# 4_USB-PD_Controller.net
KiCad netlist of a schematic drawn in Altium Designer
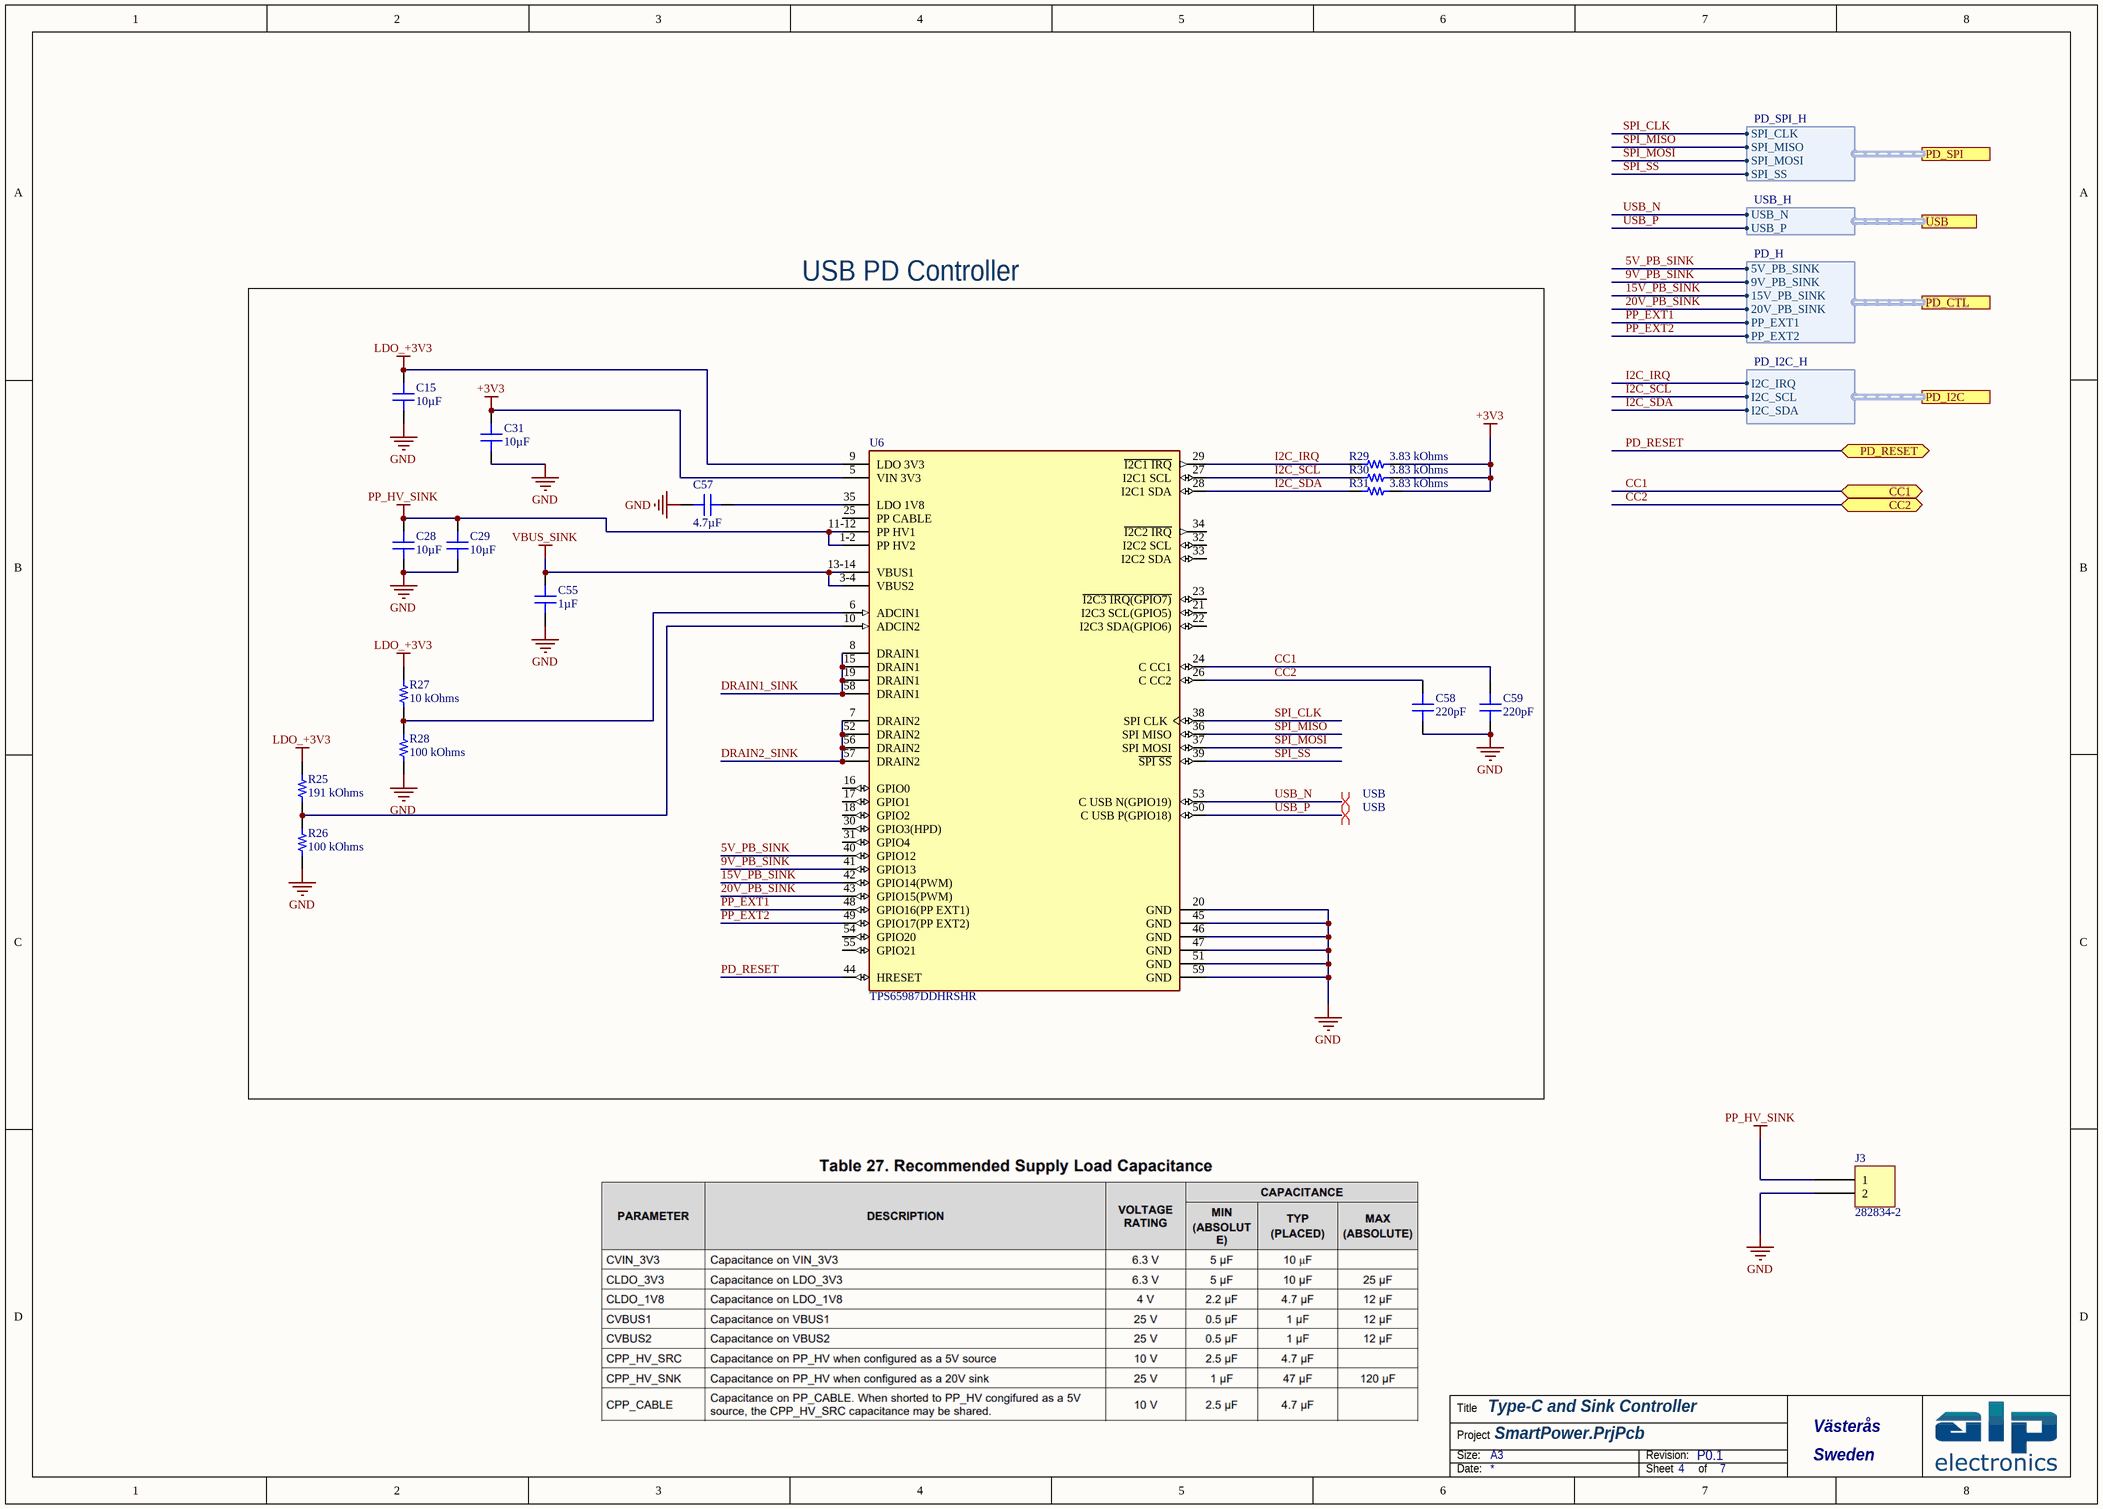
[diagram p0: [4] USB-PD Controller.SchDoc]

(export (version "E")
  (design (tool "Eeschema 10.0.6"))
  (components
    (comp (ref "C15")
      (value "10µF")
      (footprint "CAP 0603_1608")
      (description "CAP CER 10UF 10V X5R 0603")
      (fields (field (name "PART NUMBER") "0603ZD106KAT2A") (field (name "MANUFACTURER") "AVX Corporation"))
      (libsource (lib "Celestial Altium Library - altium_library") (part "Capacitor"))
    )
    (comp (ref "C28")
      (value "10µF")
      (footprint "CAP 1206_3216 - 1.8MM")
      (description "CAP CER 10UF 25V X7R 1206")
      (fields
        (field (name "PART NUMBER") "1206BB106K250NGX072T")
        (field (name "MANUFACTURER") "Knowles Novacap")
      )
      (libsource (lib "Celestial Altium Library - altium_library") (part "Capacitor"))
    )
    (comp (ref "C29")
      (value "10µF")
      (footprint "CAP 1206_3216 - 1.8MM")
      (description "CAP CER 10UF 25V X7R 1206")
      (fields
        (field (name "PART NUMBER") "1206BB106K250NGX072T")
        (field (name "MANUFACTURER") "Knowles Novacap")
      )
      (libsource (lib "Celestial Altium Library - altium_library") (part "Capacitor"))
    )
    (comp (ref "C31")
      (value "10µF")
      (footprint "CAP 0603_1608")
      (description "CAP CER 10UF 10V X5R 0603")
      (fields (field (name "PART NUMBER") "0603ZD106KAT2A") (field (name "MANUFACTURER") "AVX Corporation"))
      (libsource (lib "Celestial Altium Library - altium_library") (part "Capacitor"))
    )
    (comp (ref "C55")
      (value "1µF")
      (footprint "CAP 1206_3216 - 0.8MM")
      (description "CAP CER 1UF 25V X7R 1206")
      (fields (field (name "PART NUMBER") "AC1206KKX7R8BB105") (field (name "MANUFACTURER") "Yageo"))
      (libsource (lib "Celestial Altium Library - altium_library") (part "Capacitor"))
    )
    (comp (ref "C57")
      (value "4.7µF")
      (footprint "CAP 0603_1608")
      (description "CAP CER 4.7UF 10V X5R 0603")
      (fields (field (name "PART NUMBER") "0603ZD475KAT2A") (field (name "MANUFACTURER") "AVX Corporation"))
      (libsource (lib "Celestial Altium Library - altium_library") (part "Capacitor"))
    )
    (comp (ref "C58")
      (value "220pF")
      (footprint "CAP 0603_1608")
      (description "CAP CER 220PF 50V C0G/NP0 0603")
      (fields
        (field (name "PART NUMBER") "500R14N221JV4T")
        (field (name "MANUFACTURER") "Johanson Dielectrics Inc.")
      )
      (libsource (lib "Celestial Altium Library - altium_library") (part "Capacitor"))
    )
    (comp (ref "C59")
      (value "220pF")
      (footprint "CAP 0603_1608")
      (description "CAP CER 220PF 50V C0G/NP0 0603")
      (fields
        (field (name "PART NUMBER") "500R14N221JV4T")
        (field (name "MANUFACTURER") "Johanson Dielectrics Inc.")
      )
      (libsource (lib "Celestial Altium Library - altium_library") (part "Capacitor"))
    )
    (comp (ref "J3")
      (value "282834-2")
      (footprint "TE 282834-2")
      (description "TERM BLK 2P SIDE ENT 2.54MM PCB")
      (fields (field (name "MANUFACTURER") "TE Connectivity AMP Connectors") (field (name "VOLTAGE") "150V"))
      (libsource (lib "Celestial Altium Library - altium_library") (part "2 Pin"))
    )
    (comp (ref "R25")
      (value "191 kOhms")
      (footprint "RES 0603_1608")
      (description "RES SMD 191K OHM 1% 1/10W 0603")
      (fields (field (name "PART NUMBER") "RC0603FR-07191KL") (field (name "MANUFACTURER") "Yageo"))
      (libsource (lib "Celestial Altium Library - altium_library") (part "Resistor"))
    )
    (comp (ref "R26")
      (value "100 kOhms")
      (footprint "RES 0603_1608")
      (description "RES SMD 100K OHM 5% 1/5W 0603")
      (fields
        (field (name "PART NUMBER") "CRGH0603J100K")
        (field (name "MANUFACTURER") "TE Connectivity Passive Product")
      )
      (libsource (lib "Celestial Altium Library - altium_library") (part "Resistor"))
    )
    (comp (ref "R27")
      (value "10 kOhms")
      (footprint "RES 0603_1608")
      (description "RES SMD 10K OHM 5% 1/10W 0603")
      (fields (field (name "PART NUMBER") "CRCW060310K0JNEA") (field (name "MANUFACTURER") "Vishay Dale"))
      (libsource (lib "Celestial Altium Library - altium_library") (part "Resistor"))
    )
    (comp (ref "R28")
      (value "100 kOhms")
      (footprint "RES 0603_1608")
      (description "RES SMD 100K OHM 5% 1/5W 0603")
      (fields
        (field (name "PART NUMBER") "CRGH0603J100K")
        (field (name "MANUFACTURER") "TE Connectivity Passive Product")
      )
      (libsource (lib "Celestial Altium Library - altium_library") (part "Resistor"))
    )
    (comp (ref "R29")
      (value "3.83 kOhms")
      (footprint "RES 0603_1608")
      (description "RES SMD 3.83K OHM 1% 1/10W 0603")
      (fields (field (name "PART NUMBER") "RC0603FR-073K83L") (field (name "MANUFACTURER") "Yageo"))
      (libsource (lib "Celestial Altium Library - altium_library") (part "Resistor"))
    )
    (comp (ref "R30")
      (value "3.83 kOhms")
      (footprint "RES 0603_1608")
      (description "RES SMD 3.83K OHM 1% 1/10W 0603")
      (fields (field (name "PART NUMBER") "RC0603FR-073K83L") (field (name "MANUFACTURER") "Yageo"))
      (libsource (lib "Celestial Altium Library - altium_library") (part "Resistor"))
    )
    (comp (ref "R31")
      (value "3.83 kOhms")
      (footprint "RES 0603_1608")
      (description "RES SMD 3.83K OHM 1% 1/10W 0603")
      (fields (field (name "PART NUMBER") "RC0603FR-073K83L") (field (name "MANUFACTURER") "Yageo"))
      (libsource (lib "Celestial Altium Library - altium_library") (part "Resistor"))
    )
    (comp (ref "U6")
      (value "TPS65987DDHRSHR")
      (footprint "FP-RSH0056E-MFG")
      (description "ACELITE 88 ROM 1.6 PROTO 7X7")
      (fields
        (field (name "OCTOPART") "https://octopart.com/tps65987ddhrshr-texas+instruments-92191376")
        (field (name "MANUFACTURER") "Texas Instruments")
      )
      (libsource (lib "Altium Content Vault") (part "ac31af8065ecbcdb16e42a170e0950f"))
    )
  )
  (nets
    (net (code "5") (name "+3V3") (class "Default")
      (node (ref "C31") (pin "2") (pinfunction "2_2") (pintype "passive"))
      (node (ref "R29") (pin "1") (pinfunction "1_1") (pintype "passive"))
      (node (ref "R30") (pin "1") (pinfunction "1_1") (pintype "passive"))
      (node (ref "R31") (pin "1") (pinfunction "1_1") (pintype "passive"))
      (node (ref "U6") (pin "5") (pinfunction "VIN_3V3_5") (pintype "power_in"))
    )
    (net (code "6") (name "/5V_PB_SINK") (class "Default")
      (node (ref "U6") (pin "40") (pinfunction "GPIO12_40") (pintype "bidirectional"))
    )
    (net (code "7") (name "/9V_PB_SINK") (class "Default")
      (node (ref "U6") (pin "41") (pinfunction "GPIO13_41") (pintype "bidirectional"))
    )
    (net (code "8") (name "/15V_PB_SINK") (class "Default")
      (node (ref "U6") (pin "42") (pinfunction "GPIO14(PWM)_42") (pintype "bidirectional"))
    )
    (net (code "9") (name "/20V_PB_SINK") (class "Default")
      (node (ref "U6") (pin "43") (pinfunction "GPIO15(PWM)_43") (pintype "bidirectional"))
    )
    (net (code "10") (name "/CC1") (class "Default")
      (node (ref "C59") (pin "2") (pinfunction "2_2") (pintype "passive"))
      (node (ref "U6") (pin "24") (pinfunction "C_CC1_24") (pintype "bidirectional"))
    )
    (net (code "11") (name "/CC2") (class "Default")
      (node (ref "C58") (pin "2") (pinfunction "2_2") (pintype "passive"))
      (node (ref "U6") (pin "26") (pinfunction "C_CC2_26") (pintype "bidirectional"))
    )
    (net (code "12") (name "/DRAIN1_SINK") (class "Default")
      (node (ref "U6") (pin "15") (pinfunction "DRAIN1_15") (pintype "passive"))
      (node (ref "U6") (pin "19") (pinfunction "DRAIN1_19") (pintype "passive"))
      (node (ref "U6") (pin "58") (pinfunction "DRAIN1_58") (pintype "passive"))
      (node (ref "U6") (pin "8") (pinfunction "DRAIN1_8") (pintype "passive"))
    )
    (net (code "13") (name "/DRAIN2_SINK") (class "Default")
      (node (ref "U6") (pin "52") (pinfunction "DRAIN2_52") (pintype "passive"))
      (node (ref "U6") (pin "56") (pinfunction "DRAIN2_56") (pintype "passive"))
      (node (ref "U6") (pin "57") (pinfunction "DRAIN2_57") (pintype "passive"))
      (node (ref "U6") (pin "7") (pinfunction "DRAIN2_7") (pintype "passive"))
    )
    (net (code "14") (name "/I2C_IRQ") (class "Default")
      (node (ref "R29") (pin "2") (pinfunction "2_2") (pintype "passive"))
      (node (ref "U6") (pin "29") (pinfunction "~{I2C1_IRQ}_29") (pintype "output"))
    )
    (net (code "15") (name "/I2C_SCL") (class "Default")
      (node (ref "R30") (pin "2") (pinfunction "2_2") (pintype "passive"))
      (node (ref "U6") (pin "27") (pinfunction "I2C1_SCL_27") (pintype "bidirectional"))
    )
    (net (code "16") (name "/I2C_SDA") (class "Default")
      (node (ref "R31") (pin "2") (pinfunction "2_2") (pintype "passive"))
      (node (ref "U6") (pin "28") (pinfunction "I2C1_SDA_28") (pintype "bidirectional"))
    )
    (net (code "17") (name "/PD_RESET") (class "Default")
      (node (ref "U6") (pin "44") (pinfunction "HRESET_44") (pintype "bidirectional"))
    )
    (net (code "18") (name "/PP_EXT1") (class "Default")
      (node (ref "U6") (pin "48") (pinfunction "GPIO16(PP_EXT1)_48") (pintype "bidirectional"))
    )
    (net (code "19") (name "/PP_EXT2") (class "Default")
      (node (ref "U6") (pin "49") (pinfunction "GPIO17(PP_EXT2)_49") (pintype "bidirectional"))
    )
    (net (code "20") (name "/SPI_CLK") (class "Default")
      (node (ref "U6") (pin "38") (pinfunction "SPI_CLK_38") (pintype "bidirectional"))
    )
    (net (code "21") (name "/SPI_MISO") (class "Default")
      (node (ref "U6") (pin "36") (pinfunction "SPI_MISO_36") (pintype "bidirectional"))
    )
    (net (code "22") (name "/SPI_MOSI") (class "Default")
      (node (ref "U6") (pin "37") (pinfunction "SPI_MOSI_37") (pintype "bidirectional"))
    )
    (net (code "23") (name "/SPI_SS") (class "Default")
      (node (ref "U6") (pin "39") (pinfunction "~{SPI_SS}_39") (pintype "bidirectional"))
    )
    (net (code "24") (name "/USB_N") (class "Default")
      (node (ref "U6") (pin "53") (pinfunction "C_USB_N(GPIO19)_53") (pintype "bidirectional"))
    )
    (net (code "25") (name "/USB_P") (class "Default")
      (node (ref "U6") (pin "50") (pinfunction "C_USB_P(GPIO18)_50") (pintype "bidirectional"))
    )
    (net (code "30") (name "GND") (class "Default")
      (node (ref "C15") (pin "1") (pinfunction "1_1") (pintype "passive"))
      (node (ref "C28") (pin "1") (pinfunction "1_1") (pintype "passive"))
      (node (ref "C29") (pin "1") (pinfunction "1_1") (pintype "passive"))
      (node (ref "C31") (pin "1") (pinfunction "1_1") (pintype "passive"))
      (node (ref "C55") (pin "1") (pinfunction "1_1") (pintype "passive"))
      (node (ref "C57") (pin "2") (pinfunction "2_2") (pintype "passive"))
      (node (ref "C58") (pin "1") (pinfunction "1_1") (pintype "passive"))
      (node (ref "C59") (pin "1") (pinfunction "1_1") (pintype "passive"))
      (node (ref "J3") (pin "2") (pinfunction "2_2") (pintype "passive"))
      (node (ref "R26") (pin "1") (pinfunction "1_1") (pintype "passive"))
      (node (ref "R28") (pin "1") (pinfunction "1_1") (pintype "passive"))
      (node (ref "U6") (pin "20") (pinfunction "GND_20") (pintype "power_in"))
      (node (ref "U6") (pin "45") (pinfunction "GND_45") (pintype "power_in"))
      (node (ref "U6") (pin "46") (pinfunction "GND_46") (pintype "power_in"))
      (node (ref "U6") (pin "47") (pinfunction "GND_47") (pintype "power_in"))
      (node (ref "U6") (pin "51") (pinfunction "GND_51") (pintype "power_in"))
      (node (ref "U6") (pin "59") (pinfunction "GND_59") (pintype "power_in"))
    )
    (net (code "31") (name "LDO_+3V3") (class "Default")
      (node (ref "C15") (pin "2") (pinfunction "2_2") (pintype "passive"))
      (node (ref "R25") (pin "2") (pinfunction "2_2") (pintype "passive"))
      (node (ref "R27") (pin "1") (pinfunction "1_1") (pintype "passive"))
      (node (ref "U6") (pin "9") (pinfunction "LDO_3V3_9") (pintype "power_in"))
    )
    (net (code "32") (name "Net-(U6-ADCIN1)") (class "Default")
      (node (ref "R27") (pin "2") (pinfunction "2_2") (pintype "passive"))
      (node (ref "R28") (pin "2") (pinfunction "2_2") (pintype "passive"))
      (node (ref "U6") (pin "6") (pinfunction "ADCIN1_6") (pintype "input"))
    )
    (net (code "33") (name "Net-(U6-ADCIN2)") (class "Default")
      (node (ref "R25") (pin "1") (pinfunction "1_1") (pintype "passive"))
      (node (ref "R26") (pin "2") (pinfunction "2_2") (pintype "passive"))
      (node (ref "U6") (pin "10") (pinfunction "ADCIN2_10") (pintype "input"))
    )
    (net (code "34") (name "Net-(U6-LDO_1V8)") (class "Default")
      (node (ref "C57") (pin "1") (pinfunction "1_1") (pintype "passive"))
      (node (ref "U6") (pin "35") (pinfunction "LDO_1V8_35") (pintype "power_in"))
    )
    (net (code "35") (name "PP_HV_SINK") (class "Default")
      (node (ref "C28") (pin "2") (pinfunction "2_2") (pintype "passive"))
      (node (ref "C29") (pin "2") (pinfunction "2_2") (pintype "passive"))
      (node (ref "J3") (pin "1") (pinfunction "1_1") (pintype "passive"))
      (node (ref "U6") (pin "1-2") (pinfunction "PP_HV2_1-2") (pintype "power_in"))
      (node (ref "U6") (pin "11-12") (pinfunction "PP_HV1_11-12") (pintype "power_in"))
    )
    (net (code "36") (name "VBUS_SINK") (class "Default")
      (node (ref "C55") (pin "2") (pinfunction "2_2") (pintype "passive"))
      (node (ref "U6") (pin "13-14") (pinfunction "VBUS1_13-14") (pintype "power_in"))
      (node (ref "U6") (pin "3-4") (pinfunction "VBUS2_3-4") (pintype "power_in"))
    )
    (net (code "37") (name "unconnected-(U6-GPIO0-Pad16)") (class "Default")
      (node (ref "U6") (pin "16") (pinfunction "GPIO0_16") (pintype "bidirectional"))
    )
    (net (code "38") (name "unconnected-(U6-GPIO1-Pad17)") (class "Default")
      (node (ref "U6") (pin "17") (pinfunction "GPIO1_17") (pintype "bidirectional"))
    )
    (net (code "39") (name "unconnected-(U6-GPIO2-Pad18)") (class "Default")
      (node (ref "U6") (pin "18") (pinfunction "GPIO2_18") (pintype "bidirectional"))
    )
    (net (code "40") (name "unconnected-(U6-GPIO3(HPD)-Pad30)") (class "Default")
      (node (ref "U6") (pin "30") (pinfunction "GPIO3(HPD)_30") (pintype "bidirectional"))
    )
    (net (code "41") (name "unconnected-(U6-GPIO4-Pad31)") (class "Default")
      (node (ref "U6") (pin "31") (pinfunction "GPIO4_31") (pintype "bidirectional"))
    )
    (net (code "42") (name "unconnected-(U6-GPIO20-Pad54)") (class "Default")
      (node (ref "U6") (pin "54") (pinfunction "GPIO20_54") (pintype "bidirectional"))
    )
    (net (code "43") (name "unconnected-(U6-GPIO21-Pad55)") (class "Default")
      (node (ref "U6") (pin "55") (pinfunction "GPIO21_55") (pintype "bidirectional"))
    )
    (net (code "44") (name "unconnected-(U6-I2C2_SCL-Pad32)") (class "Default")
      (node (ref "U6") (pin "32") (pinfunction "I2C2_SCL_32") (pintype "bidirectional"))
    )
    (net (code "45") (name "unconnected-(U6-I2C2_SDA-Pad33)") (class "Default")
      (node (ref "U6") (pin "33") (pinfunction "I2C2_SDA_33") (pintype "bidirectional"))
    )
    (net (code "46") (name "unconnected-(U6-I2C3_SCL(GPIO5)-Pad21)") (class "Default")
      (node (ref "U6") (pin "21") (pinfunction "I2C3_SCL(GPIO5)_21") (pintype "bidirectional"))
    )
    (net (code "47") (name "unconnected-(U6-I2C3_SDA(GPIO6)-Pad22)") (class "Default")
      (node (ref "U6") (pin "22") (pinfunction "I2C3_SDA(GPIO6)_22") (pintype "bidirectional"))
    )
    (net (code "48") (name "unconnected-(U6-PP_CABLE-Pad25)") (class "Default")
      (node (ref "U6") (pin "25") (pinfunction "PP_CABLE_25") (pintype "power_in"))
    )
    (net (code "49") (name "unconnected-(U6-~{I2C2_IRQ}-Pad34)") (class "Default")
      (node (ref "U6") (pin "34") (pinfunction "~{I2C2_IRQ}_34") (pintype "output"))
    )
    (net (code "50") (name "unconnected-(U6-~{I2C3_IRQ(GPIO7)}-Pad23)") (class "Default")
      (node (ref "U6") (pin "23") (pinfunction "~{I2C3_IRQ(GPIO7)}_23") (pintype "bidirectional"))
    )
  )
)
